# THAT340_FET.net
KiCad netlist of a schematic drawn in EAGLE
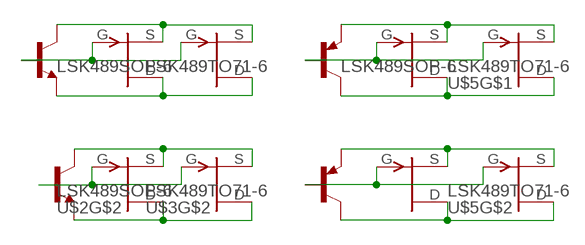
[diagram p0: schematic, sheet 1]

(export (version "E")
  (design (tool "Eeschema 10.0.6"))
  (components
    (comp (ref "U$1")
      (value "TRANSISTOR-ARRAYS_THAT340")
      (footprint "eagle-import:TRANSISTOR-ARRAYS_DIP254P762X510-14")
      (libsource (lib "eagle-import") (part "TRANSISTOR-ARRAYS_THAT340"))
    )
    (comp (ref "U$2")
      (value "LSK489SOP-6")
      (footprint "eagle-import:SOT-23-6")
      (libsource (lib "eagle-import") (part "LSK489SOP-6"))
    )
    (comp (ref "U$3")
      (value "LSK489TO71-6")
      (footprint "eagle-import:TO71-6")
      (libsource (lib "eagle-import") (part "LSK489TO71-6"))
    )
    (comp (ref "U$4")
      (value "LSK489SOP-6")
      (footprint "eagle-import:SOT-23-6")
      (libsource (lib "eagle-import") (part "LSK489SOP-6"))
    )
    (comp (ref "U$5")
      (value "LSK489TO71-6")
      (footprint "eagle-import:TO71-6")
      (libsource (lib "eagle-import") (part "LSK489TO71-6"))
    )
  )
  (nets
    (net (code "1") (name "Net-(U$1A-B)") (class "Default")
      (node (ref "U$1") (pin "2") (pinfunction "B_2") (pintype "passive"))
      (node (ref "U$2") (pin "1") (pinfunction "G_1") (pintype "passive"))
      (node (ref "U$3") (pin "3") (pinfunction "G_3") (pintype "passive"))
    )
    (net (code "2") (name "Net-(U$1A-C)") (class "Default")
      (node (ref "U$1") (pin "1") (pinfunction "C_1") (pintype "passive"))
      (node (ref "U$2") (pin "3") (pinfunction "S_3") (pintype "passive"))
      (node (ref "U$3") (pin "1") (pinfunction "S_1") (pintype "passive"))
    )
    (net (code "3") (name "Net-(U$1A-E)") (class "Default")
      (node (ref "U$1") (pin "3") (pinfunction "E_3") (pintype "passive"))
      (node (ref "U$2") (pin "2") (pinfunction "D_2") (pintype "passive"))
      (node (ref "U$3") (pin "2") (pinfunction "D_2") (pintype "passive"))
    )
    (net (code "4") (name "Net-(U$1B-B)") (class "Default")
      (node (ref "U$1") (pin "13") (pinfunction "B_13") (pintype "passive"))
      (node (ref "U$2") (pin "4") (pinfunction "G_4") (pintype "passive"))
      (node (ref "U$3") (pin "7") (pinfunction "G_7") (pintype "passive"))
    )
    (net (code "5") (name "Net-(U$1B-C)") (class "Default")
      (node (ref "U$1") (pin "14") (pinfunction "C_14") (pintype "passive"))
      (node (ref "U$2") (pin "6") (pinfunction "S_6") (pintype "passive"))
      (node (ref "U$3") (pin "5") (pinfunction "S_5") (pintype "passive"))
    )
    (net (code "6") (name "Net-(U$1B-E)") (class "Default")
      (node (ref "U$1") (pin "12") (pinfunction "E_12") (pintype "passive"))
      (node (ref "U$2") (pin "5") (pinfunction "D_5") (pintype "passive"))
      (node (ref "U$3") (pin "6") (pinfunction "D_6") (pintype "passive"))
    )
    (net (code "7") (name "Net-(U$1C-B)") (class "Default")
      (node (ref "U$1") (pin "6") (pinfunction "B_6") (pintype "passive"))
      (node (ref "U$4") (pin "1") (pinfunction "G_1") (pintype "passive"))
      (node (ref "U$5") (pin "3") (pinfunction "G_3") (pintype "passive"))
    )
    (net (code "8") (name "Net-(U$1C-C)") (class "Default")
      (node (ref "U$1") (pin "7") (pinfunction "C_7") (pintype "passive"))
      (node (ref "U$4") (pin "2") (pinfunction "D_2") (pintype "passive"))
      (node (ref "U$5") (pin "2") (pinfunction "D_2") (pintype "passive"))
    )
    (net (code "9") (name "Net-(U$1C-E)") (class "Default")
      (node (ref "U$1") (pin "5") (pinfunction "E_5") (pintype "passive"))
      (node (ref "U$4") (pin "3") (pinfunction "S_3") (pintype "passive"))
      (node (ref "U$5") (pin "1") (pinfunction "S_1") (pintype "passive"))
    )
    (net (code "10") (name "Net-(U$1D-B)") (class "Default")
      (node (ref "U$1") (pin "9") (pinfunction "B_9") (pintype "passive"))
      (node (ref "U$4") (pin "4") (pinfunction "G_4") (pintype "passive"))
      (node (ref "U$5") (pin "7") (pinfunction "G_7") (pintype "passive"))
    )
    (net (code "11") (name "Net-(U$1D-C)") (class "Default")
      (node (ref "U$1") (pin "8") (pinfunction "C_8") (pintype "passive"))
      (node (ref "U$4") (pin "5") (pinfunction "D_5") (pintype "passive"))
      (node (ref "U$5") (pin "6") (pinfunction "D_6") (pintype "passive"))
    )
    (net (code "12") (name "Net-(U$1D-E)") (class "Default")
      (node (ref "U$1") (pin "10") (pinfunction "E_10") (pintype "passive"))
      (node (ref "U$4") (pin "6") (pinfunction "S_6") (pintype "passive"))
      (node (ref "U$5") (pin "5") (pinfunction "S_5") (pintype "passive"))
    )
  )
)
